# cc2652r_v2_1_rs.net
KiCad netlist of a schematic drawn in EAGLE
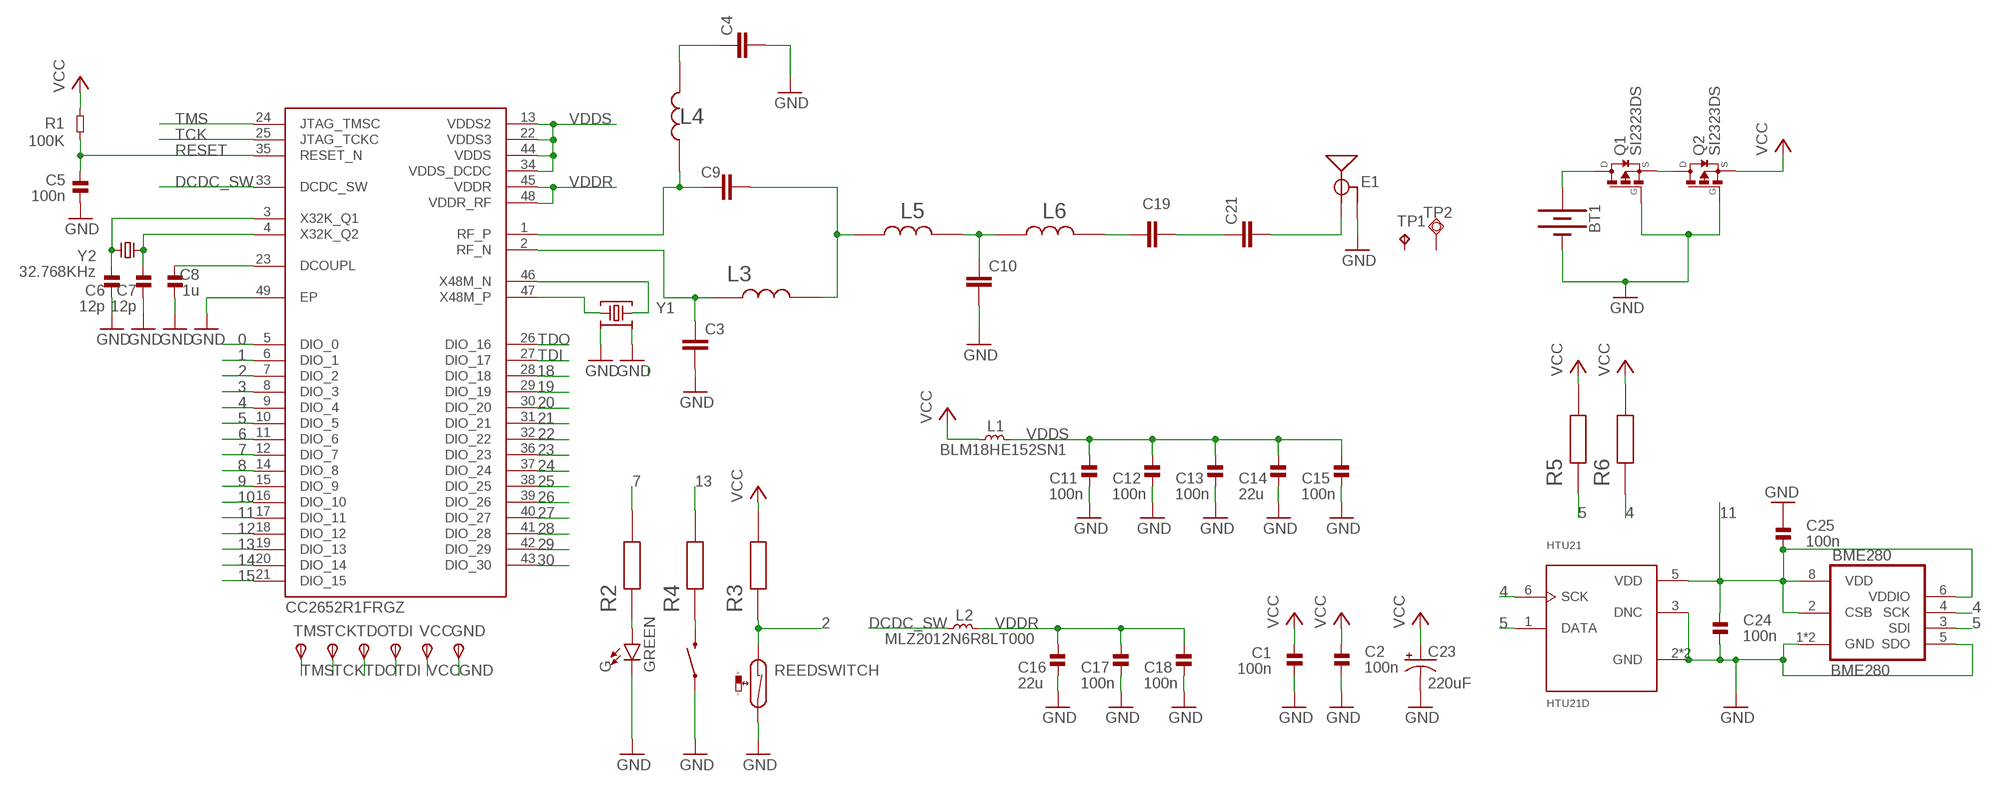
[diagram p0: schematic, sheet 1]

(export (version "E")
  (design (tool "Eeschema 10.0.6"))
  (components
    (comp (ref "BME280")
      (value "BME280")
      (footprint "eagle-import:BME280")
      (libsource (lib "eagle-import") (part "BME280"))
    )
    (comp (ref "BT1")
      (value "BATTERY-20MM_SMD")
      (footprint "eagle-import:BATTCON_20MM")
      (libsource (lib "eagle-import") (part "BATTERY-20MM_SMD"))
    )
    (comp (ref "C1")
      (value "100n")
      (footprint "eagle-import:_PKG_C_0402")
      (libsource (lib "eagle-import") (part "CAP-0402"))
    )
    (comp (ref "C2")
      (value "100n")
      (footprint "eagle-import:_PKG_C_0402")
      (libsource (lib "eagle-import") (part "CAP-0402"))
    )
    (comp (ref "C3")
      (value "1pf")
      (footprint "eagle-import:CAPC1005X40N")
      (fields (field (name "MF") "Yageo") (field (name "MP") "RC0402FR-073M6L"))
      (libsource (lib "eagle-import") (part "CAP0402"))
    )
    (comp (ref "C4")
      (value "12pF")
      (footprint "eagle-import:CAPC1005X40N")
      (fields (field (name "MF") "Yageo") (field (name "MP") "RC0402FR-073M6L"))
      (libsource (lib "eagle-import") (part "CAP0402"))
    )
    (comp (ref "C5")
      (value "100n")
      (footprint "eagle-import:_PKG_C_0402")
      (libsource (lib "eagle-import") (part "CAP-0402"))
    )
    (comp (ref "C6")
      (value "12p")
      (footprint "eagle-import:_PKG_C_0402")
      (libsource (lib "eagle-import") (part "CAP-0402"))
    )
    (comp (ref "C7")
      (value "12p")
      (footprint "eagle-import:_PKG_C_0402")
      (libsource (lib "eagle-import") (part "CAP-0402"))
    )
    (comp (ref "C8")
      (value "1u")
      (footprint "eagle-import:_PKG_C_0402")
      (libsource (lib "eagle-import") (part "CAP-0402"))
    )
    (comp (ref "C9")
      (value "1pF")
      (footprint "eagle-import:CAPC1005X40N")
      (fields (field (name "MF") "Yageo") (field (name "MP") "RC0402FR-073M6L"))
      (libsource (lib "eagle-import") (part "CAP0402"))
    )
    (comp (ref "C10")
      (value "1pF")
      (footprint "eagle-import:CAPC1005X40N")
      (fields (field (name "MF") "Yageo") (field (name "MP") "RC0402FR-073M6L"))
      (libsource (lib "eagle-import") (part "CAP0402"))
    )
    (comp (ref "C11")
      (value "100n")
      (footprint "eagle-import:_PKG_C_0402")
      (libsource (lib "eagle-import") (part "CAP-0402"))
    )
    (comp (ref "C12")
      (value "100n")
      (footprint "eagle-import:_PKG_C_0402")
      (libsource (lib "eagle-import") (part "CAP-0402"))
    )
    (comp (ref "C13")
      (value "100n")
      (footprint "eagle-import:_PKG_C_0402")
      (libsource (lib "eagle-import") (part "CAP-0402"))
    )
    (comp (ref "C14")
      (value "22u")
      (footprint "eagle-import:_PKG_C_0805")
      (libsource (lib "eagle-import") (part "CAP-0805"))
    )
    (comp (ref "C15")
      (value "100n")
      (footprint "eagle-import:_PKG_C_0402")
      (libsource (lib "eagle-import") (part "CAP-0402"))
    )
    (comp (ref "C16")
      (value "22u")
      (footprint "eagle-import:_PKG_C_0805")
      (libsource (lib "eagle-import") (part "CAP-0805"))
    )
    (comp (ref "C17")
      (value "100n")
      (footprint "eagle-import:_PKG_C_0402")
      (libsource (lib "eagle-import") (part "CAP-0402"))
    )
    (comp (ref "C18")
      (value "100n")
      (footprint "eagle-import:_PKG_C_0402")
      (libsource (lib "eagle-import") (part "CAP-0402"))
    )
    (comp (ref "C19")
      (value "12pF")
      (footprint "eagle-import:CAPC1005X40N")
      (fields (field (name "MF") "Yageo") (field (name "MP") "RC0402FR-073M6L"))
      (libsource (lib "eagle-import") (part "CAP0402"))
    )
    (comp (ref "C21")
      (value "1.8pF")
      (footprint "eagle-import:CAPC1005X40N")
      (fields (field (name "MF") "Yageo") (field (name "MP") "RC0402FR-073M6L"))
      (libsource (lib "eagle-import") (part "CAP0402"))
    )
    (comp (ref "C23")
      (value "220uF")
      (footprint "eagle-import:EIA3528")
      (libsource (lib "eagle-import") (part "68UF-POLAR-EIA3528-10V-10%(TANT)"))
    )
    (comp (ref "C24")
      (value "100n")
      (footprint "eagle-import:_PKG_C_0402")
      (libsource (lib "eagle-import") (part "CAP-0402"))
    )
    (comp (ref "C25")
      (value "100n")
      (footprint "eagle-import:_PKG_C_0402")
      (libsource (lib "eagle-import") (part "CAP-0402"))
    )
    (comp (ref "E1")
      (value "ANTENNA-GROUNDEDTRACE-15.2MM")
      (footprint "eagle-import:TRACE_ANTENNA_2.4GHZ_15.2MM")
      (libsource (lib "eagle-import") (part "ANTENNA-GROUNDEDTRACE-15.2MM"))
    )
    (comp (ref "G")
      (value "GREEN")
      (footprint "eagle-import:LED-0603")
      (libsource (lib "eagle-import") (part "LED-GREEN0603"))
    )
    (comp (ref "GND")
      (value "TPSTP11R")
      (footprint "eagle-import:TP11R")
      (libsource (lib "eagle-import") (part "TPSTP11R"))
    )
    (comp (ref "HTU21")
      (value "HTU21D")
      (footprint "eagle-import:QFN100P300X300X100-7N")
      (fields (field (name "COMMENT") "CAT-HSC0004") (field (name "MF") "TE Connectivity"))
      (libsource (lib "eagle-import") (part "HTU21D"))
    )
    (comp (ref "IC3")
      (value "CC2652R1FRGZ")
      (footprint "eagle-import:QFN50P700X700X100-49N")
      (fields
        (field (name "ARROW_PART_NUMBER") "CC2652R1FRGZT")
        (field (name "MOUSER_PART_NUMBER") "595-CC2652R1FRGZT")
      )
      (libsource (lib "eagle-import") (part "CC2652R1FRGZT"))
    )
    (comp (ref "L1")
      (value "BLM18HE152SN1")
      (footprint "eagle-import:_PKG_L_0603")
      (libsource (lib "eagle-import") (part "INDUCTOR-0603"))
    )
    (comp (ref "L2")
      (value "MLZ2012N6R8LT000")
      (footprint "eagle-import:_PKG_C_0805")
      (libsource (lib "eagle-import") (part "INDUCTOR-0805"))
    )
    (comp (ref "L3")
      (value "2.4nH")
      (footprint "eagle-import:INDC1005X40N")
      (fields (field (name "MF") "Yageo") (field (name "MP") "RC0402FR-073M6L"))
      (libsource (lib "eagle-import") (part "IND0402IND0402"))
    )
    (comp (ref "L4")
      (value "2.4nH")
      (footprint "eagle-import:INDC1005X40N")
      (fields (field (name "MF") "Yageo") (field (name "MP") "RC0402FR-073M6L"))
      (libsource (lib "eagle-import") (part "IND0402IND0402"))
    )
    (comp (ref "L5")
      (value "2nH")
      (footprint "eagle-import:INDC1005X40N")
      (fields (field (name "MF") "Yageo") (field (name "MP") "RC0402FR-073M6L"))
      (libsource (lib "eagle-import") (part "IND0402IND0402"))
    )
    (comp (ref "L6")
      (value "2nH")
      (footprint "eagle-import:INDC1005X40N")
      (fields (field (name "MF") "Yageo") (field (name "MP") "RC0402FR-073M6L"))
      (libsource (lib "eagle-import") (part "IND0402IND0402"))
    )
    (comp (ref "Q1")
      (value "SI2323DS")
      (footprint "eagle-import:SOT23")
      (fields (field (name "MF") "Vishay Siliconix"))
      (libsource (lib "eagle-import") (part "SI2323DS"))
    )
    (comp (ref "Q2")
      (value "SI2323DS")
      (footprint "eagle-import:SOT23")
      (fields (field (name "MF") "Vishay Siliconix"))
      (libsource (lib "eagle-import") (part "SI2323DS"))
    )
    (comp (ref "R1")
      (value "100K")
      (footprint "eagle-import:_PKG_C_0402")
      (libsource (lib "eagle-import") (part "RES-0402"))
    )
    (comp (ref "R2")
      (value "2.2k")
      (footprint "eagle-import:RESC1005X40N")
      (fields (field (name "MF") "Yageo") (field (name "MP") "RC0402FR-073M6L"))
      (libsource (lib "eagle-import") (part "RES0402"))
    )
    (comp (ref "R3")
      (value "510k")
      (footprint "eagle-import:RESC1005X40N")
      (fields (field (name "MF") "Yageo") (field (name "MP") "RC0402FR-073M6L"))
      (libsource (lib "eagle-import") (part "RES0402"))
    )
    (comp (ref "R4")
      (value "100Ohm")
      (footprint "eagle-import:RESC1005X40N")
      (fields (field (name "MF") "Yageo") (field (name "MP") "RC0402FR-073M6L"))
      (libsource (lib "eagle-import") (part "RES0402"))
    )
    (comp (ref "R5")
      (value "10k")
      (footprint "eagle-import:RESC1005X40N")
      (fields (field (name "MF") "Yageo") (field (name "MP") "RC0402FR-073M6L"))
      (libsource (lib "eagle-import") (part "RES0402"))
    )
    (comp (ref "R6")
      (value "10k")
      (footprint "eagle-import:RESC1005X40N")
      (fields (field (name "MF") "Yageo") (field (name "MP") "RC0402FR-073M6L"))
      (libsource (lib "eagle-import") (part "RES0402"))
    )
    (comp (ref "REEDSWITCH")
      (value "REED-SWITCH-MK6-5-B")
      (footprint "eagle-import:MK6-5")
      (fields (field (name "MF") "MEDER") (field (name "MPN") "MK6-5-B"))
      (libsource (lib "eagle-import") (part "REED-SWITCH-MK6-5-B"))
    )
    (comp (ref "SW1")
      (value "MOMENTARY-SWITCH-SPST-SMD-4.6X2.8MM")
      (footprint "eagle-import:TACTILE_SWITCH_SMD_4.6X2.8MM")
      (libsource (lib "eagle-import") (part "MOMENTARY-SWITCH-SPST-SMD-4.6X2.8MM"))
    )
    (comp (ref "TCK")
      (value "TPSTP11R")
      (footprint "eagle-import:TP11R")
      (libsource (lib "eagle-import") (part "TPSTP11R"))
    )
    (comp (ref "TDI")
      (value "TPSTP11R")
      (footprint "eagle-import:TP11R")
      (libsource (lib "eagle-import") (part "TPSTP11R"))
    )
    (comp (ref "TDO")
      (value "TPSTP11R")
      (footprint "eagle-import:TP11R")
      (libsource (lib "eagle-import") (part "TPSTP11R"))
    )
    (comp (ref "TMS")
      (value "TPSTP11R")
      (footprint "eagle-import:TP11R")
      (libsource (lib "eagle-import") (part "TPSTP11R"))
    )
    (comp (ref "TP1")
      (value "TPTP06SQ")
      (footprint "eagle-import:TP05SQ")
      (libsource (lib "eagle-import") (part "TPTP06SQ"))
    )
    (comp (ref "TP2")
      (value "TPSQTP15SQ")
      (footprint "eagle-import:TP15SQ")
      (libsource (lib "eagle-import") (part "TPSQTP15SQ"))
    )
    (comp (ref "VCC")
      (value "TPSTP11R")
      (footprint "eagle-import:TP11R")
      (libsource (lib "eagle-import") (part "TPSTP11R"))
    )
    (comp (ref "Y1")
      (value "Q22FA12800150")
      (footprint "eagle-import:XTAL-4P-2016")
      (fields (field (name "DIGIKEY_PART") "1253-2042-1-ND") (field (name "MFG_PART") "CX2016DB48000C0FPLC1"))
      (libsource (lib "eagle-import") (part "48.000MHZ_CX2016DB48000C0FPLC1"))
    )
    (comp (ref "Y2")
      (value "32.768KHz")
      (footprint "eagle-import:XTAL-2P-3215")
      (fields (field (name "LCSC_PART") "C32346") (field (name "MFG_PART") "Q13FC1350000400"))
      (libsource (lib "eagle-import") (part "32.768KHZ_Q13FC1350000400"))
    )
  )
  (nets
    (net (code "1") (name "/0") (class "Default")
      (node (ref "IC3") (pin "5") (pinfunction "DIO_0_5") (pintype "bidirectional"))
    )
    (net (code "2") (name "/1") (class "Default")
      (node (ref "IC3") (pin "6") (pinfunction "DIO_1_6") (pintype "bidirectional"))
    )
    (net (code "3") (name "/2") (class "Default")
      (node (ref "IC3") (pin "7") (pinfunction "DIO_2_7") (pintype "bidirectional"))
      (node (ref "R3") (pin "1") (pinfunction "1_1") (pintype "passive"))
      (node (ref "REEDSWITCH") (pin "1") (pinfunction "1_1") (pintype "passive"))
    )
    (net (code "4") (name "/3") (class "Default")
      (node (ref "IC3") (pin "8") (pinfunction "DIO_3_8") (pintype "bidirectional"))
    )
    (net (code "5") (name "/4") (class "Default")
      (node (ref "BME280") (pin "4") (pinfunction "SCK_4") (pintype "bidirectional"))
      (node (ref "HTU21") (pin "6") (pinfunction "SCK_6") (pintype "input"))
      (node (ref "IC3") (pin "9") (pinfunction "DIO_4_9") (pintype "bidirectional"))
      (node (ref "R6") (pin "1") (pinfunction "1_1") (pintype "passive"))
    )
    (net (code "6") (name "/5") (class "Default")
      (node (ref "BME280") (pin "3") (pinfunction "SDI_3") (pintype "bidirectional"))
      (node (ref "HTU21") (pin "1") (pinfunction "DATA_1") (pintype "bidirectional"))
      (node (ref "IC3") (pin "10") (pinfunction "DIO_5_10") (pintype "bidirectional"))
      (node (ref "R5") (pin "1") (pinfunction "1_1") (pintype "passive"))
    )
    (net (code "7") (name "/6") (class "Default")
      (node (ref "IC3") (pin "11") (pinfunction "DIO_6_11") (pintype "bidirectional"))
    )
    (net (code "8") (name "/7") (class "Default")
      (node (ref "IC3") (pin "12") (pinfunction "DIO_7_12") (pintype "bidirectional"))
      (node (ref "R2") (pin "2") (pinfunction "2_2") (pintype "passive"))
    )
    (net (code "9") (name "/8") (class "Default")
      (node (ref "IC3") (pin "14") (pinfunction "DIO_8_14") (pintype "bidirectional"))
    )
    (net (code "10") (name "/9") (class "Default")
      (node (ref "IC3") (pin "15") (pinfunction "DIO_9_15") (pintype "bidirectional"))
    )
    (net (code "11") (name "/10") (class "Default")
      (node (ref "IC3") (pin "16") (pinfunction "DIO_10_16") (pintype "bidirectional"))
    )
    (net (code "12") (name "/11") (class "Default")
      (node (ref "BME280") (pin "2") (pinfunction "CSB_2") (pintype "input"))
      (node (ref "BME280") (pin "6") (pinfunction "VDDIO_6") (pintype "power_in"))
      (node (ref "BME280") (pin "8") (pinfunction "VDD_8") (pintype "power_in"))
      (node (ref "C24") (pin "2") (pinfunction "2_2") (pintype "passive"))
      (node (ref "C25") (pin "1") (pinfunction "1_1") (pintype "passive"))
      (node (ref "HTU21") (pin "5") (pinfunction "VDD_5") (pintype "power_in"))
      (node (ref "IC3") (pin "17") (pinfunction "DIO_11_17") (pintype "bidirectional"))
    )
    (net (code "13") (name "/12") (class "Default")
      (node (ref "IC3") (pin "18") (pinfunction "DIO_12_18") (pintype "bidirectional"))
    )
    (net (code "14") (name "/13") (class "Default")
      (node (ref "IC3") (pin "19") (pinfunction "DIO_13_19") (pintype "bidirectional"))
      (node (ref "R4") (pin "2") (pinfunction "2_2") (pintype "passive"))
    )
    (net (code "15") (name "/14") (class "Default")
      (node (ref "IC3") (pin "20") (pinfunction "DIO_14_20") (pintype "bidirectional"))
    )
    (net (code "16") (name "/15") (class "Default")
      (node (ref "IC3") (pin "21") (pinfunction "DIO_15_21") (pintype "bidirectional"))
    )
    (net (code "17") (name "/18") (class "Default")
      (node (ref "IC3") (pin "28") (pinfunction "DIO_18_28") (pintype "bidirectional"))
    )
    (net (code "18") (name "/19") (class "Default")
      (node (ref "IC3") (pin "29") (pinfunction "DIO_19_29") (pintype "bidirectional"))
    )
    (net (code "19") (name "/20") (class "Default")
      (node (ref "IC3") (pin "30") (pinfunction "DIO_20_30") (pintype "bidirectional"))
    )
    (net (code "20") (name "/21") (class "Default")
      (node (ref "IC3") (pin "31") (pinfunction "DIO_21_31") (pintype "bidirectional"))
    )
    (net (code "21") (name "/22") (class "Default")
      (node (ref "IC3") (pin "32") (pinfunction "DIO_22_32") (pintype "bidirectional"))
    )
    (net (code "22") (name "/23") (class "Default")
      (node (ref "IC3") (pin "36") (pinfunction "DIO_23_36") (pintype "bidirectional"))
    )
    (net (code "23") (name "/24") (class "Default")
      (node (ref "IC3") (pin "37") (pinfunction "DIO_24_37") (pintype "bidirectional"))
    )
    (net (code "24") (name "/25") (class "Default")
      (node (ref "IC3") (pin "38") (pinfunction "DIO_25_38") (pintype "bidirectional"))
    )
    (net (code "25") (name "/26") (class "Default")
      (node (ref "IC3") (pin "39") (pinfunction "DIO_26_39") (pintype "bidirectional"))
    )
    (net (code "26") (name "/27") (class "Default")
      (node (ref "IC3") (pin "40") (pinfunction "DIO_27_40") (pintype "bidirectional"))
    )
    (net (code "27") (name "/28") (class "Default")
      (node (ref "IC3") (pin "41") (pinfunction "DIO_28_41") (pintype "bidirectional"))
    )
    (net (code "28") (name "/29") (class "Default")
      (node (ref "IC3") (pin "42") (pinfunction "DIO_29_42") (pintype "bidirectional"))
    )
    (net (code "29") (name "/30") (class "Default")
      (node (ref "IC3") (pin "43") (pinfunction "DIO_30_43") (pintype "bidirectional"))
    )
    (net (code "30") (name "/DCDC_SW") (class "Default")
      (node (ref "IC3") (pin "33") (pinfunction "DCDC_SW_33") (pintype "bidirectional"))
      (node (ref "L2") (pin "1") (pinfunction "1_1") (pintype "passive"))
    )
    (net (code "31") (name "/RESET") (class "Default")
      (node (ref "C5") (pin "2") (pinfunction "2_2") (pintype "passive"))
      (node (ref "IC3") (pin "35") (pinfunction "RESET_N_35") (pintype "bidirectional"))
      (node (ref "R1") (pin "1") (pinfunction "1_1") (pintype "passive"))
    )
    (net (code "32") (name "/TCK") (class "Default")
      (node (ref "IC3") (pin "25") (pinfunction "JTAG_TCKC_25") (pintype "bidirectional"))
      (node (ref "TCK") (pin "TP") (pinfunction "PP_TP") (pintype "input"))
    )
    (net (code "33") (name "/TDI") (class "Default")
      (node (ref "IC3") (pin "27") (pinfunction "DIO_17_27") (pintype "bidirectional"))
      (node (ref "TDI") (pin "TP") (pinfunction "PP_TP") (pintype "input"))
    )
    (net (code "34") (name "/TDO") (class "Default")
      (node (ref "IC3") (pin "26") (pinfunction "DIO_16_26") (pintype "bidirectional"))
      (node (ref "TDO") (pin "TP") (pinfunction "PP_TP") (pintype "input"))
    )
    (net (code "35") (name "/TMS") (class "Default")
      (node (ref "IC3") (pin "24") (pinfunction "JTAG_TMSC_24") (pintype "bidirectional"))
      (node (ref "TMS") (pin "TP") (pinfunction "PP_TP") (pintype "input"))
    )
    (net (code "36") (name "/VDDR") (class "Default")
      (node (ref "C16") (pin "1") (pinfunction "1_1") (pintype "passive"))
      (node (ref "C17") (pin "1") (pinfunction "1_1") (pintype "passive"))
      (node (ref "C18") (pin "1") (pinfunction "1_1") (pintype "passive"))
      (node (ref "IC3") (pin "45") (pinfunction "VDDR_45") (pintype "bidirectional"))
      (node (ref "IC3") (pin "48") (pinfunction "VDDR_RF_48") (pintype "bidirectional"))
      (node (ref "L2") (pin "2") (pinfunction "2_2") (pintype "passive"))
    )
    (net (code "37") (name "/VDDS") (class "Default")
      (node (ref "C11") (pin "1") (pinfunction "1_1") (pintype "passive"))
      (node (ref "C12") (pin "1") (pinfunction "1_1") (pintype "passive"))
      (node (ref "C13") (pin "1") (pinfunction "1_1") (pintype "passive"))
      (node (ref "C14") (pin "1") (pinfunction "1_1") (pintype "passive"))
      (node (ref "C15") (pin "1") (pinfunction "1_1") (pintype "passive"))
      (node (ref "IC3") (pin "13") (pinfunction "VDDS2_13") (pintype "bidirectional"))
      (node (ref "IC3") (pin "22") (pinfunction "VDDS3_22") (pintype "bidirectional"))
      (node (ref "IC3") (pin "34") (pinfunction "VDDS_DCDC_34") (pintype "bidirectional"))
      (node (ref "IC3") (pin "44") (pinfunction "VDDS_44") (pintype "bidirectional"))
      (node (ref "L1") (pin "2") (pinfunction "2_2") (pintype "passive"))
    )
    (net (code "38") (name "GND") (class "Default")
      (node (ref "BME280") (pin "1") (pinfunction "GND_1") (pintype "power_in"))
      (node (ref "BME280") (pin "5") (pinfunction "SDO_5") (pintype "input"))
      (node (ref "BME280") (pin "7") (pinfunction "GND_7") (pintype "power_in"))
      (node (ref "BT1") (pin "2") (pinfunction "-_2") (pintype "power_in"))
      (node (ref "C1") (pin "1") (pinfunction "1_1") (pintype "passive"))
      (node (ref "C10") (pin "2") (pinfunction "2_2") (pintype "passive"))
      (node (ref "C11") (pin "2") (pinfunction "2_2") (pintype "passive"))
      (node (ref "C12") (pin "2") (pinfunction "2_2") (pintype "passive"))
      (node (ref "C13") (pin "2") (pinfunction "2_2") (pintype "passive"))
      (node (ref "C14") (pin "2") (pinfunction "2_2") (pintype "passive"))
      (node (ref "C15") (pin "2") (pinfunction "2_2") (pintype "passive"))
      (node (ref "C16") (pin "2") (pinfunction "2_2") (pintype "passive"))
      (node (ref "C17") (pin "2") (pinfunction "2_2") (pintype "passive"))
      (node (ref "C18") (pin "2") (pinfunction "2_2") (pintype "passive"))
      (node (ref "C2") (pin "1") (pinfunction "1_1") (pintype "passive"))
      (node (ref "C23") (pin "C") (pinfunction "-_C") (pintype "passive"))
      (node (ref "C24") (pin "1") (pinfunction "1_1") (pintype "passive"))
      (node (ref "C25") (pin "2") (pinfunction "2_2") (pintype "passive"))
      (node (ref "C3") (pin "2") (pinfunction "2_2") (pintype "passive"))
      (node (ref "C4") (pin "2") (pinfunction "2_2") (pintype "passive"))
      (node (ref "C5") (pin "1") (pinfunction "1_1") (pintype "passive"))
      (node (ref "C6") (pin "1") (pinfunction "1_1") (pintype "passive"))
      (node (ref "C7") (pin "1") (pinfunction "1_1") (pintype "passive"))
      (node (ref "C8") (pin "1") (pinfunction "1_1") (pintype "passive"))
      (node (ref "E1") (pin "GND") (pinfunction "GND_GND") (pintype "bidirectional"))
      (node (ref "G") (pin "C") (pinfunction "C_C") (pintype "passive"))
      (node (ref "GND") (pin "TP") (pinfunction "PP_TP") (pintype "input"))
      (node (ref "HTU21") (pin "2") (pinfunction "GND_2") (pintype "passive"))
      (node (ref "HTU21") (pin "3") (pinfunction "DNC_3") (pintype "bidirectional"))
      (node (ref "HTU21") (pin "PAD") (pinfunction "GND_PAD") (pintype "passive"))
      (node (ref "IC3") (pin "49") (pinfunction "EP_49") (pintype "bidirectional"))
      (node (ref "Q1") (pin "1") (pinfunction "G_1") (pintype "passive"))
      (node (ref "Q2") (pin "1") (pinfunction "G_1") (pintype "passive"))
      (node (ref "REEDSWITCH") (pin "2") (pinfunction "2_2") (pintype "passive"))
      (node (ref "SW1") (pin "1") (pinfunction "1_1") (pintype "passive"))
      (node (ref "SW1") (pin "2") (pinfunction "1_2") (pintype "passive"))
      (node (ref "Y1") (pin "2") (pinfunction "2_2") (pintype "bidirectional"))
      (node (ref "Y1") (pin "4") (pinfunction "4_4") (pintype "bidirectional"))
    )
    (net (code "39") (name "Net-(BT1-+)") (class "Default")
      (node (ref "BT1") (pin "1") (pinfunction "+_1") (pintype "power_in"))
      (node (ref "Q1") (pin "3") (pinfunction "D_3") (pintype "passive"))
    )
    (net (code "40") (name "Net-(C4-Pad1)") (class "Default")
      (node (ref "C4") (pin "1") (pinfunction "1_1") (pintype "passive"))
      (node (ref "L4") (pin "2") (pinfunction "2_2") (pintype "passive"))
    )
    (net (code "41") (name "Net-(C9-Pad2)") (class "Default")
      (node (ref "C9") (pin "2") (pinfunction "2_2") (pintype "passive"))
      (node (ref "L3") (pin "2") (pinfunction "2_2") (pintype "passive"))
      (node (ref "L5") (pin "1") (pinfunction "1_1") (pintype "passive"))
    )
    (net (code "42") (name "Net-(C10-Pad1)") (class "Default")
      (node (ref "C10") (pin "1") (pinfunction "1_1") (pintype "passive"))
      (node (ref "L5") (pin "2") (pinfunction "2_2") (pintype "passive"))
      (node (ref "L6") (pin "1") (pinfunction "1_1") (pintype "passive"))
    )
    (net (code "43") (name "Net-(C19-Pad1)") (class "Default")
      (node (ref "C19") (pin "1") (pinfunction "1_1") (pintype "passive"))
      (node (ref "L6") (pin "2") (pinfunction "2_2") (pintype "passive"))
    )
    (net (code "44") (name "Net-(C19-Pad2)") (class "Default")
      (node (ref "C19") (pin "2") (pinfunction "2_2") (pintype "passive"))
      (node (ref "C21") (pin "1") (pinfunction "1_1") (pintype "passive"))
    )
    (net (code "45") (name "Net-(E1-SIGNAL)") (class "Default")
      (node (ref "C21") (pin "2") (pinfunction "2_2") (pintype "passive"))
      (node (ref "E1") (pin "ANT") (pinfunction "SIGNAL_ANT") (pintype "bidirectional"))
    )
    (net (code "46") (name "Net-(G-PadA)") (class "Default")
      (node (ref "G") (pin "A") (pinfunction "A_A") (pintype "passive"))
      (node (ref "R2") (pin "1") (pinfunction "1_1") (pintype "passive"))
    )
    (net (code "47") (name "Net-(IC3-DCOUPL)") (class "Default")
      (node (ref "C8") (pin "2") (pinfunction "2_2") (pintype "passive"))
      (node (ref "IC3") (pin "23") (pinfunction "DCOUPL_23") (pintype "bidirectional"))
    )
    (net (code "48") (name "Net-(IC3-RF_N)") (class "Default")
      (node (ref "C3") (pin "1") (pinfunction "1_1") (pintype "passive"))
      (node (ref "IC3") (pin "2") (pinfunction "RF_N_2") (pintype "bidirectional"))
      (node (ref "L3") (pin "1") (pinfunction "1_1") (pintype "passive"))
    )
    (net (code "49") (name "Net-(IC3-RF_P)") (class "Default")
      (node (ref "C9") (pin "1") (pinfunction "1_1") (pintype "passive"))
      (node (ref "IC3") (pin "1") (pinfunction "RF_P_1") (pintype "bidirectional"))
      (node (ref "L4") (pin "1") (pinfunction "1_1") (pintype "passive"))
    )
    (net (code "50") (name "Net-(IC3-X32K_Q1)") (class "Default")
      (node (ref "C6") (pin "2") (pinfunction "2_2") (pintype "passive"))
      (node (ref "IC3") (pin "3") (pinfunction "X32K_Q1_3") (pintype "bidirectional"))
      (node (ref "Y2") (pin "1") (pinfunction "1_1") (pintype "passive"))
    )
    (net (code "51") (name "Net-(IC3-X32K_Q2)") (class "Default")
      (node (ref "C7") (pin "2") (pinfunction "2_2") (pintype "passive"))
      (node (ref "IC3") (pin "4") (pinfunction "X32K_Q2_4") (pintype "bidirectional"))
      (node (ref "Y2") (pin "2") (pinfunction "2_2") (pintype "passive"))
    )
    (net (code "52") (name "Net-(IC3-X48M_N)") (class "Default")
      (node (ref "IC3") (pin "46") (pinfunction "X48M_N_46") (pintype "bidirectional"))
      (node (ref "Y1") (pin "3") (pinfunction "3_3") (pintype "passive"))
    )
    (net (code "53") (name "Net-(IC3-X48M_P)") (class "Default")
      (node (ref "IC3") (pin "47") (pinfunction "X48M_P_47") (pintype "bidirectional"))
      (node (ref "Y1") (pin "1") (pinfunction "1_1") (pintype "passive"))
    )
    (net (code "54") (name "Net-(Q1-S)") (class "Default")
      (node (ref "Q1") (pin "2") (pinfunction "S_2") (pintype "passive"))
      (node (ref "Q2") (pin "3") (pinfunction "D_3") (pintype "passive"))
    )
    (net (code "55") (name "Net-(R4-Pad1)") (class "Default")
      (node (ref "R4") (pin "1") (pinfunction "1_1") (pintype "passive"))
      (node (ref "SW1") (pin "3") (pinfunction "2_3") (pintype "passive"))
      (node (ref "SW1") (pin "4") (pinfunction "2_4") (pintype "passive"))
    )
    (net (code "56") (name "VCC") (class "Default")
      (node (ref "C1") (pin "2") (pinfunction "2_2") (pintype "passive"))
      (node (ref "C2") (pin "2") (pinfunction "2_2") (pintype "passive"))
      (node (ref "C23") (pin "A") (pinfunction "+_A") (pintype "passive"))
      (node (ref "L1") (pin "1") (pinfunction "1_1") (pintype "passive"))
      (node (ref "Q2") (pin "2") (pinfunction "S_2") (pintype "passive"))
      (node (ref "R1") (pin "2") (pinfunction "2_2") (pintype "passive"))
      (node (ref "R3") (pin "2") (pinfunction "2_2") (pintype "passive"))
      (node (ref "R5") (pin "2") (pinfunction "2_2") (pintype "passive"))
      (node (ref "R6") (pin "2") (pinfunction "2_2") (pintype "passive"))
      (node (ref "VCC") (pin "TP") (pinfunction "PP_TP") (pintype "input"))
    )
    (net (code "57") (name "unconnected-(TP1-PadTP)") (class "Default")
      (node (ref "TP1") (pin "TP") (pinfunction "TP_TP") (pintype "input"))
    )
    (net (code "58") (name "unconnected-(TP2-PadTP)") (class "Default")
      (node (ref "TP2") (pin "TP") (pinfunction "TP_TP") (pintype "input"))
    )
  )
)
